# SH5_-_3_3V_LINEAR_REGULATOR.net
KiCad netlist of a schematic drawn in Altium Designer
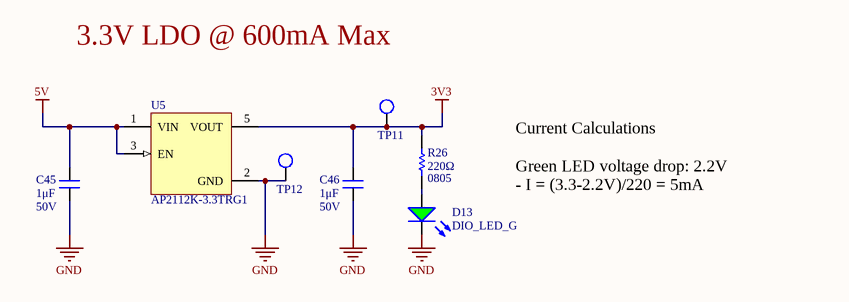
[diagram p0: SH5 - 3.3V LINEAR REGULATOR.SchDoc]

(export (version "E")
  (design (tool "Eeschema 10.0.6"))
  (components
    (comp (ref "C45")
      (value "1μF")
      (footprint "CAP2012")
      (description "CAP CER 1UF 50V X7R 0805")
      (fields
        (field (name "VOLTAGE RATING") "50V")
        (field (name "LCSC PART #") "C28323")
        (field (name "Comment") "CAP_1uF_50V_0805")
      )
      (libsource (lib "UWRT_Schematic_Library_2020") (part "CAP_1uF_50V_0805"))
    )
    (comp (ref "C46")
      (value "1μF")
      (footprint "CAP2012")
      (description "CAP CER 1UF 50V X7R 0805")
      (fields
        (field (name "VOLTAGE RATING") "50V")
        (field (name "LCSC PART #") "C28323")
        (field (name "Comment") "CAP_1uF_50V_0805")
      )
      (libsource (lib "UWRT_Schematic_Library_2020") (part "CAP_1uF_50V_0805"))
    )
    (comp (ref "D13")
      (value "DIO_LED_G")
      (footprint "LED_0805_GREEN")
      (description "LED GREEN DIFFUSED 0805 SMD")
      (libsource (lib "UWRT_Schematic_Library_2020") (part "DIO_LED_G"))
    )
    (comp (ref "R26")
      (value "220Ω")
      (footprint "RESC0805")
      (description "RES SMD 220 OHM 5% 1/2W 0805")
      (fields
        (field (name "TOLERANCE") "5%")
        (field (name "LCSC PART #") "C17557")
        (field (name "PACKAGE/FOOTPRINT") "0805")
      )
      (libsource (lib "UWRT_Schematic_Library_2020") (part "RES_220Ω_0805_5%"))
    )
    (comp (ref "TP11")
      (value "TESTPOINT_LOOP")
      (footprint "TESTPOINT_LOOP")
      (description "PC TEST POINT MINIATURE WHITE")
      (libsource (lib "UWRT_Schematic_Library_2020") (part "TESTPOINT_LOOP"))
    )
    (comp (ref "TP12")
      (value "TESTPOINT_LOOP")
      (footprint "TESTPOINT_LOOP")
      (description "PC TEST POINT MINIATURE WHITE")
      (libsource (lib "UWRT_Schematic_Library_2020") (part "TESTPOINT_LOOP"))
    )
    (comp (ref "U5")
      (value "LDO_3.3V_600mA")
      (footprint "SOT95P285X140-5N")
      (description "IC REG LINEAR 3.3V 600MA SOT25")
      (fields
        (field (name "MANUFACTURER PART NUMBER 1") "AP2112K-3.3TRG1")
        (field (name "LCSC PART #") "C51118")
      )
      (libsource (lib "UWRT_Schematic_Library_2020") (part "LDO_3.3V_600mA"))
    )
  )
  (nets
    (net (code "1") (name "3V3") (class "Default")
      (node (ref "C46") (pin "2") (pinfunction "2_2") (pintype "passive"))
      (node (ref "R26") (pin "2") (pinfunction "2_2") (pintype "passive"))
      (node (ref "TP11") (pin "1") (pintype "passive"))
      (node (ref "U5") (pin "5") (pinfunction "VOUT_5") (pintype "power_in"))
    )
    (net (code "2") (name "5V") (class "Default")
      (node (ref "C45") (pin "2") (pinfunction "2_2") (pintype "passive"))
      (node (ref "U5") (pin "1") (pinfunction "VIN_1") (pintype "power_in"))
      (node (ref "U5") (pin "3") (pinfunction "EN_3") (pintype "input"))
    )
    (net (code "3") (name "GND") (class "Default")
      (node (ref "C45") (pin "1") (pinfunction "1_1") (pintype "passive"))
      (node (ref "C46") (pin "1") (pinfunction "1_1") (pintype "passive"))
      (node (ref "D13") (pin "2") (pinfunction "K_2") (pintype "passive"))
      (node (ref "TP12") (pin "1") (pintype "passive"))
      (node (ref "U5") (pin "2") (pinfunction "GND_2") (pintype "power_in"))
    )
    (net (code "4") (name "Net-(D13-A)") (class "Default")
      (node (ref "D13") (pin "1") (pinfunction "A_1") (pintype "passive"))
      (node (ref "R26") (pin "1") (pinfunction "1_1") (pintype "passive"))
    )
  )
)
